# untitled.net
KiCad netlist of a schematic drawn in EAGLE
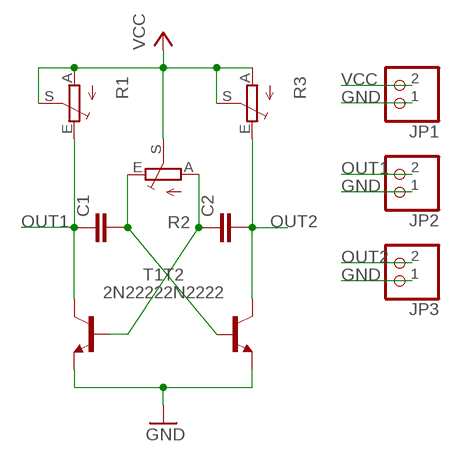
[diagram p0: schematic, sheet 1]

(export (version "E")
  (design (tool "Eeschema 10.0.6"))
  (components
    (comp (ref "C1")
      (value "C-EU025-025X050")
      (footprint "eagle-import:C025-025X050")
      (libsource (lib "eagle-import") (part "C-EU025-025X050"))
    )
    (comp (ref "C2")
      (value "C-EU025-025X050")
      (footprint "eagle-import:C025-025X050")
      (libsource (lib "eagle-import") (part "C-EU025-025X050"))
    )
    (comp (ref "JP1")
      (value "PINHD-1X2")
      (footprint "eagle-import:1X02")
      (libsource (lib "eagle-import") (part "PINHD-1X2"))
    )
    (comp (ref "JP2")
      (value "PINHD-1X2")
      (footprint "eagle-import:1X02")
      (libsource (lib "eagle-import") (part "PINHD-1X2"))
    )
    (comp (ref "JP3")
      (value "PINHD-1X2")
      (footprint "eagle-import:1X02")
      (libsource (lib "eagle-import") (part "PINHD-1X2"))
    )
    (comp (ref "R1")
      (value "TRIM_EU-CA9V")
      (footprint "eagle-import:CA9V")
      (libsource (lib "eagle-import") (part "TRIM_EU-CA9V"))
    )
    (comp (ref "R2")
      (value "TRIM_EU-CA9V")
      (footprint "eagle-import:CA9V")
      (libsource (lib "eagle-import") (part "TRIM_EU-CA9V"))
    )
    (comp (ref "R3")
      (value "TRIM_EU-CA9V")
      (footprint "eagle-import:CA9V")
      (libsource (lib "eagle-import") (part "TRIM_EU-CA9V"))
    )
    (comp (ref "T1")
      (value "2N2222")
      (footprint "eagle-import:TO18")
      (libsource (lib "eagle-import") (part "2N2222"))
    )
    (comp (ref "T2")
      (value "2N2222")
      (footprint "eagle-import:TO18")
      (libsource (lib "eagle-import") (part "2N2222"))
    )
  )
  (nets
    (net (code "1") (name "/OUT1") (class "Default")
      (node (ref "C1") (pin "1") (pinfunction "1_1") (pintype "passive"))
      (node (ref "JP2") (pin "2") (pinfunction "2_2") (pintype "passive"))
      (node (ref "R1") (pin "E") (pinfunction "E_E") (pintype "passive"))
      (node (ref "T1") (pin "3") (pinfunction "C_3") (pintype "passive"))
    )
    (net (code "2") (name "/OUT2") (class "Default")
      (node (ref "C2") (pin "2") (pinfunction "2_2") (pintype "passive"))
      (node (ref "JP3") (pin "2") (pinfunction "2_2") (pintype "passive"))
      (node (ref "R3") (pin "E") (pinfunction "E_E") (pintype "passive"))
      (node (ref "T2") (pin "3") (pinfunction "C_3") (pintype "passive"))
    )
    (net (code "3") (name "GND") (class "Default")
      (node (ref "JP1") (pin "1") (pinfunction "1_1") (pintype "passive"))
      (node (ref "JP2") (pin "1") (pinfunction "1_1") (pintype "passive"))
      (node (ref "JP3") (pin "1") (pinfunction "1_1") (pintype "passive"))
      (node (ref "T1") (pin "1") (pinfunction "E_1") (pintype "passive"))
      (node (ref "T2") (pin "1") (pinfunction "E_1") (pintype "passive"))
    )
    (net (code "4") (name "Net-(T1-B)") (class "Default")
      (node (ref "C2") (pin "1") (pinfunction "1_1") (pintype "passive"))
      (node (ref "R2") (pin "A") (pinfunction "A_A") (pintype "passive"))
      (node (ref "T1") (pin "2") (pinfunction "B_2") (pintype "passive"))
    )
    (net (code "5") (name "Net-(T2-B)") (class "Default")
      (node (ref "C1") (pin "2") (pinfunction "2_2") (pintype "passive"))
      (node (ref "R2") (pin "E") (pinfunction "E_E") (pintype "passive"))
      (node (ref "T2") (pin "2") (pinfunction "B_2") (pintype "passive"))
    )
    (net (code "6") (name "VCC") (class "Default")
      (node (ref "JP1") (pin "2") (pinfunction "2_2") (pintype "passive"))
      (node (ref "R1") (pin "A") (pinfunction "A_A") (pintype "passive"))
      (node (ref "R1") (pin "S") (pinfunction "S_S") (pintype "passive"))
      (node (ref "R2") (pin "S") (pinfunction "S_S") (pintype "passive"))
      (node (ref "R3") (pin "A") (pinfunction "A_A") (pintype "passive"))
      (node (ref "R3") (pin "S") (pinfunction "S_S") (pintype "passive"))
    )
  )
)
